# FOTA_MicroController.net
KiCad netlist of a schematic drawn in Altium Designer
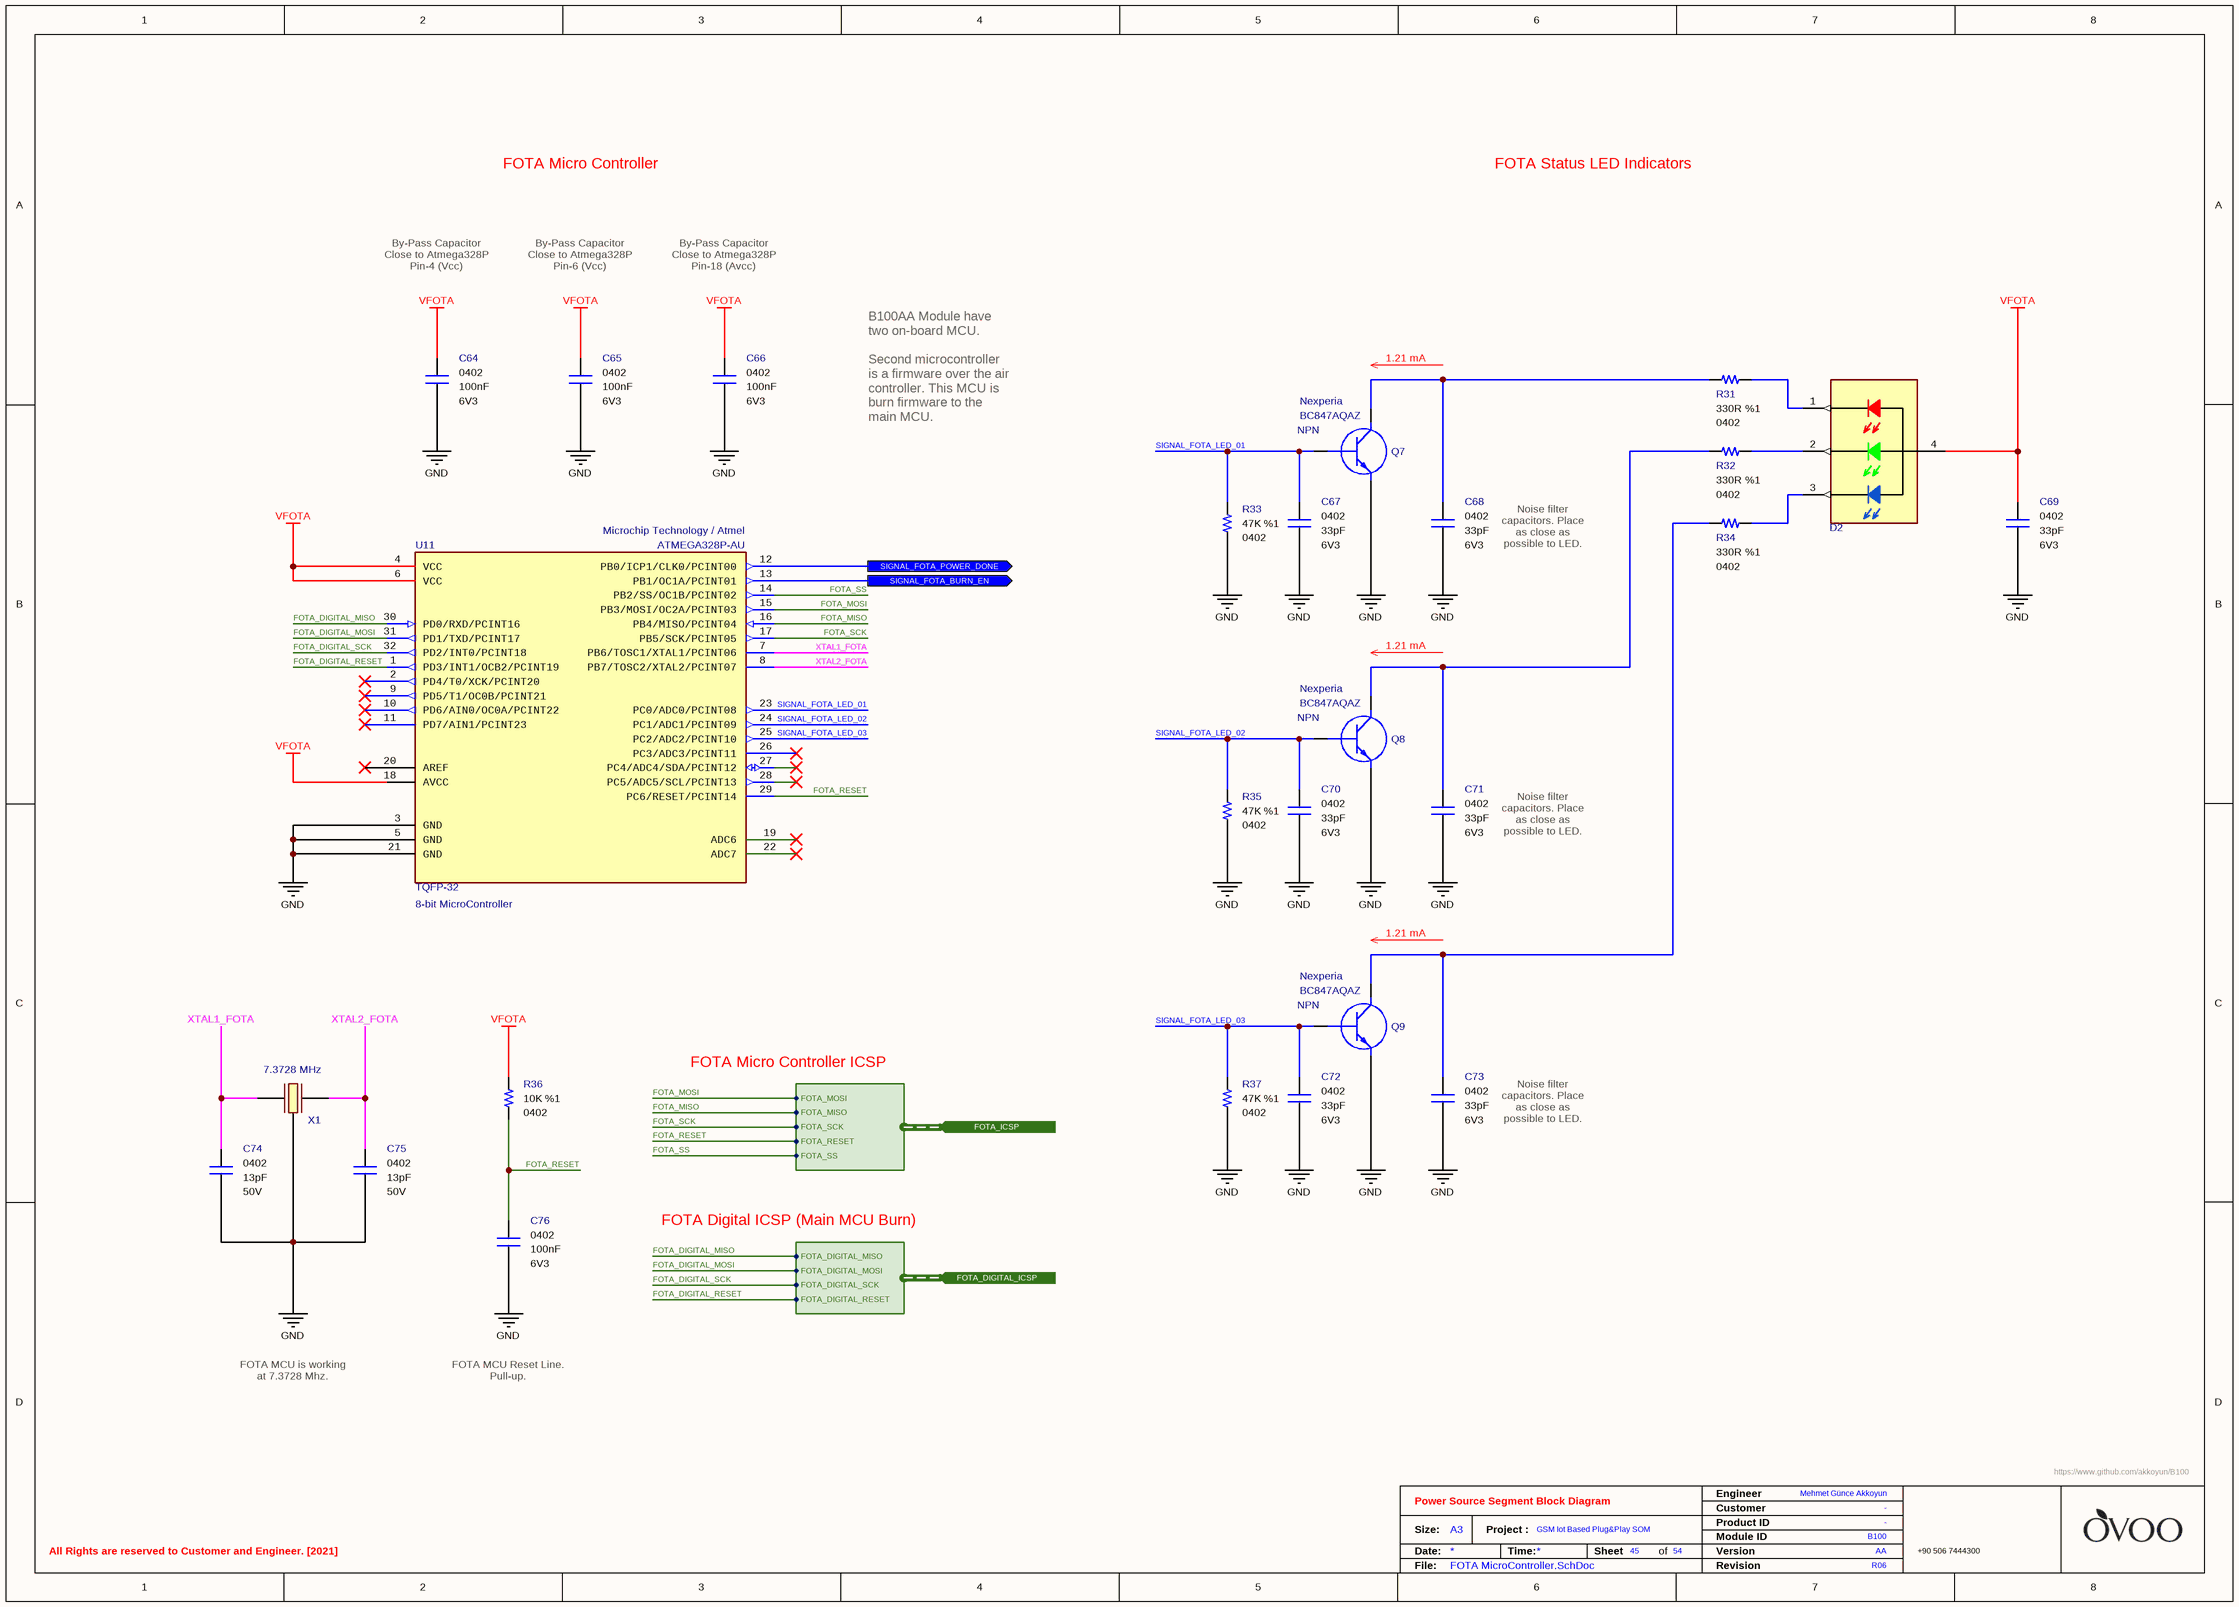
[diagram p0: FOTA MicroController.SchDoc]

(export (version "E")
  (design (tool "Eeschema 10.0.6"))
  (components
    (comp (ref "C64")
      (value "100nF")
      (footprint "CAPACITOR_0402")
      (description "Capacitor - 100nF [0402-6V3] (Ceramic)")
      (fields
        (field (name "TOLERANCE") "%10")
        (field (name "CASE") "0402")
        (field (name "VOLTAGE") "6V3")
        (field (name "MANUFACTURER PART NUMBER") "04026D104KAT4A")
      )
      (libsource (lib "Ovoo_Library") (part "Capacitor - 100nF [0402-6V3]"))
    )
    (comp (ref "C65")
      (value "100nF")
      (footprint "CAPACITOR_0402")
      (description "Capacitor - 100nF [0402-6V3] (Ceramic)")
      (fields
        (field (name "TOLERANCE") "%10")
        (field (name "CASE") "0402")
        (field (name "VOLTAGE") "6V3")
        (field (name "MANUFACTURER PART NUMBER") "04026D104KAT4A")
      )
      (libsource (lib "Ovoo_Library") (part "Capacitor - 100nF [0402-6V3]"))
    )
    (comp (ref "C66")
      (value "100nF")
      (footprint "CAPACITOR_0402")
      (description "Capacitor - 100nF [0402-6V3] (Ceramic)")
      (fields
        (field (name "TOLERANCE") "%10")
        (field (name "CASE") "0402")
        (field (name "VOLTAGE") "6V3")
        (field (name "MANUFACTURER PART NUMBER") "04026D104KAT4A")
      )
      (libsource (lib "Ovoo_Library") (part "Capacitor - 100nF [0402-6V3]"))
    )
    (comp (ref "C67")
      (value "33pF")
      (footprint "CAPACITOR_0402")
      (description "Capacitor - 33pF [0402] (Ceramic)")
      (fields
        (field (name "CASE") "0402")
        (field (name "TOLERANCE") "10%")
        (field (name "VOLTAGE") "6V3")
        (field (name "MANUFACTURER PART NUMBER") "C0402C330J9RACAUTO")
      )
      (libsource (lib "Ovoo_Library") (part "Capacitor - 33pF [0402-6V3]"))
    )
    (comp (ref "C68")
      (value "33pF")
      (footprint "CAPACITOR_0402")
      (description "Capacitor - 33pF [0402] (Ceramic)")
      (fields
        (field (name "CASE") "0402")
        (field (name "TOLERANCE") "10%")
        (field (name "VOLTAGE") "6V3")
        (field (name "MANUFACTURER PART NUMBER") "C0402C330J9RACAUTO")
      )
      (libsource (lib "Ovoo_Library") (part "Capacitor - 33pF [0402-6V3]"))
    )
    (comp (ref "C69")
      (value "33pF")
      (footprint "CAPACITOR_0402")
      (description "Capacitor - 33pF [0402] (Ceramic)")
      (fields
        (field (name "CASE") "0402")
        (field (name "TOLERANCE") "10%")
        (field (name "VOLTAGE") "6V3")
        (field (name "MANUFACTURER PART NUMBER") "C0402C330J9RACAUTO")
      )
      (libsource (lib "Ovoo_Library") (part "Capacitor - 33pF [0402-6V3]"))
    )
    (comp (ref "C70")
      (value "33pF")
      (footprint "CAPACITOR_0402")
      (description "Capacitor - 33pF [0402] (Ceramic)")
      (fields
        (field (name "CASE") "0402")
        (field (name "TOLERANCE") "10%")
        (field (name "VOLTAGE") "6V3")
        (field (name "MANUFACTURER PART NUMBER") "C0402C330J9RACAUTO")
      )
      (libsource (lib "Ovoo_Library") (part "Capacitor - 33pF [0402-6V3]"))
    )
    (comp (ref "C71")
      (value "33pF")
      (footprint "CAPACITOR_0402")
      (description "Capacitor - 33pF [0402] (Ceramic)")
      (fields
        (field (name "CASE") "0402")
        (field (name "TOLERANCE") "10%")
        (field (name "VOLTAGE") "6V3")
        (field (name "MANUFACTURER PART NUMBER") "C0402C330J9RACAUTO")
      )
      (libsource (lib "Ovoo_Library") (part "Capacitor - 33pF [0402-6V3]"))
    )
    (comp (ref "C72")
      (value "33pF")
      (footprint "CAPACITOR_0402")
      (description "Capacitor - 33pF [0402] (Ceramic)")
      (fields
        (field (name "CASE") "0402")
        (field (name "TOLERANCE") "10%")
        (field (name "VOLTAGE") "6V3")
        (field (name "MANUFACTURER PART NUMBER") "C0402C330J9RACAUTO")
      )
      (libsource (lib "Ovoo_Library") (part "Capacitor - 33pF [0402-6V3]"))
    )
    (comp (ref "C73")
      (value "33pF")
      (footprint "CAPACITOR_0402")
      (description "Capacitor - 33pF [0402] (Ceramic)")
      (fields
        (field (name "CASE") "0402")
        (field (name "TOLERANCE") "10%")
        (field (name "VOLTAGE") "6V3")
        (field (name "MANUFACTURER PART NUMBER") "C0402C330J9RACAUTO")
      )
      (libsource (lib "Ovoo_Library") (part "Capacitor - 33pF [0402-6V3]"))
    )
    (comp (ref "C74")
      (value "13pF")
      (footprint "CAPACITOR_0402")
      (description "Capacitor - 13pF [0402] (Ceramic)")
      (fields
        (field (name "TOLERANCE") "1%")
        (field (name "VOLTAGE") "50V")
        (field (name "CASE") "0402")
        (field (name "MANUFACTURER PART NUMBER") "CBR04C130F5GAC")
      )
      (libsource (lib "Ovoo_Library") (part "Capacitor - 13pF [0402-50V]"))
    )
    (comp (ref "C75")
      (value "13pF")
      (footprint "CAPACITOR_0402")
      (description "Capacitor - 13pF [0402] (Ceramic)")
      (fields
        (field (name "TOLERANCE") "1%")
        (field (name "VOLTAGE") "50V")
        (field (name "CASE") "0402")
        (field (name "MANUFACTURER PART NUMBER") "CBR04C130F5GAC")
      )
      (libsource (lib "Ovoo_Library") (part "Capacitor - 13pF [0402-50V]"))
    )
    (comp (ref "C76")
      (value "100nF")
      (footprint "CAPACITOR_0402")
      (description "Capacitor - 100nF [0402-6V3] (Ceramic)")
      (fields
        (field (name "TOLERANCE") "%10")
        (field (name "CASE") "0402")
        (field (name "VOLTAGE") "6V3")
        (field (name "MANUFACTURER PART NUMBER") "04026D104KAT4A")
      )
      (libsource (lib "Ovoo_Library") (part "Capacitor - 100nF [0402-6V3]"))
    )
    (comp (ref "D2")
      (value "150066M153000")
      (footprint "Wurth_0606")
      (description "Standard LEDs - SMD PICOLED series Red LED")
      (fields (field (name "MOUSER PART NUMBER") "710-150066M153000"))
      (libsource (lib "Ovoo_Library") (part "Diode - RGB LED (150066M153000)"))
    )
    (comp (ref "Q7")
      (value "BC847AQAZ")
      (footprint "SOT1215")
      (description "Bipolar NPN Transistors")
      (fields
        (field (name "POLARITY") "NPN")
        (field (name "MANUFACTURER NAME") "Nexperia")
        (field (name "MANUFACTURER PART NUMBER") "BC847AQAZ")
      )
      (libsource (lib "Ovoo_Library") (part "Transistor - BC847"))
    )
    (comp (ref "Q8")
      (value "BC847AQAZ")
      (footprint "SOT1215")
      (description "Bipolar NPN Transistors")
      (fields
        (field (name "POLARITY") "NPN")
        (field (name "MANUFACTURER NAME") "Nexperia")
        (field (name "MANUFACTURER PART NUMBER") "BC847AQAZ")
      )
      (libsource (lib "Ovoo_Library") (part "Transistor - BC847"))
    )
    (comp (ref "Q9")
      (value "BC847AQAZ")
      (footprint "SOT1215")
      (description "Bipolar NPN Transistors")
      (fields
        (field (name "POLARITY") "NPN")
        (field (name "MANUFACTURER NAME") "Nexperia")
        (field (name "MANUFACTURER PART NUMBER") "BC847AQAZ")
      )
      (libsource (lib "Ovoo_Library") (part "Transistor - BC847"))
    )
    (comp (ref "R31")
      (value "330R")
      (footprint "RESISTOR_0402")
      (description "Thick Film Resistors - SMD 1/16 W 330 Ohm 1%")
      (fields
        (field (name "TOLERANCE") "%1")
        (field (name "CASE") "0402")
        (field (name "MANUFACTURER PART NUMBER") "CRCW0402330RFKED")
        (field (name "MOUSER PART NUMBER") "71-CRCW0402-330-E3")
      )
      (libsource (lib "Ovoo_Library") (part "Resistor - 330R"))
    )
    (comp (ref "R32")
      (value "330R")
      (footprint "RESISTOR_0402")
      (description "Thick Film Resistors - SMD 1/16 W 330 Ohm 1%")
      (fields
        (field (name "TOLERANCE") "%1")
        (field (name "CASE") "0402")
        (field (name "MANUFACTURER PART NUMBER") "CRCW0402330RFKED")
        (field (name "MOUSER PART NUMBER") "71-CRCW0402-330-E3")
      )
      (libsource (lib "Ovoo_Library") (part "Resistor - 330R"))
    )
    (comp (ref "R33")
      (value "47K")
      (footprint "RESISTOR_0402")
      (description "Thick Film Resistors - SMD 1/16 W 47 Kohms 1%")
      (fields
        (field (name "TOLERANCE") "%1")
        (field (name "CASE") "0402")
        (field (name "MANUFACTURER PART NUMBER") "CRCW040247K0FKED")
        (field (name "Comment") "47K - 0402 - %1 - 1/16W")
      )
      (libsource (lib "Ovoo_Library") (part "Resistor - 47K"))
    )
    (comp (ref "R34")
      (value "330R")
      (footprint "RESISTOR_0402")
      (description "Thick Film Resistors - SMD 1/16 W 330 Ohm 1%")
      (fields
        (field (name "TOLERANCE") "%1")
        (field (name "CASE") "0402")
        (field (name "MANUFACTURER PART NUMBER") "CRCW0402330RFKED")
        (field (name "MOUSER PART NUMBER") "71-CRCW0402-330-E3")
      )
      (libsource (lib "Ovoo_Library") (part "Resistor - 330R"))
    )
    (comp (ref "R35")
      (value "47K")
      (footprint "RESISTOR_0402")
      (description "Thick Film Resistors - SMD 1/16 W 47 Kohms 1%")
      (fields
        (field (name "TOLERANCE") "%1")
        (field (name "CASE") "0402")
        (field (name "MANUFACTURER PART NUMBER") "CRCW040247K0FKED")
        (field (name "Comment") "47K - 0402 - %1 - 1/16W")
      )
      (libsource (lib "Ovoo_Library") (part "Resistor - 47K"))
    )
    (comp (ref "R36")
      (value "10K")
      (footprint "RESISTOR_0402")
      (description "Thick Film Resistors - SMD 1/16 W 10 Kohms 1%")
      (fields
        (field (name "TOLERANCE") "%1")
        (field (name "CASE") "0402")
        (field (name "MANUFACTURER PART NUMBER") "CRCW040210K0FKED")
        (field (name "MOUSER PART NUMBER") "71-CRCW0402-10K-E3")
      )
      (libsource (lib "Ovoo_Library") (part "Resistor - 10K"))
    )
    (comp (ref "R37")
      (value "47K")
      (footprint "RESISTOR_0402")
      (description "Thick Film Resistors - SMD 1/16 W 47 Kohms 1%")
      (fields
        (field (name "TOLERANCE") "%1")
        (field (name "CASE") "0402")
        (field (name "MANUFACTURER PART NUMBER") "CRCW040247K0FKED")
        (field (name "Comment") "47K - 0402 - %1 - 1/16W")
      )
      (libsource (lib "Ovoo_Library") (part "Resistor - 47K"))
    )
    (comp (ref "U11")
      (value "8-bit MicroController")
      (footprint "TQFP32")
      (description "8-bit Microcontrollers - MCU 32KB In-system Flash 20MHz 1.8V-5.5V")
      (fields
        (field (name "CASE") "TQFP-32")
        (field (name "MOUSER PART NUMBER") "556-ATMEGA328P-AU")
        (field (name "MANUFACTURER PART NUMBER") "ATMEGA328P-AU")
        (field (name "MANUFACTURER NAME") "Microchip Technology / Atmel")
      )
      (libsource (lib "Ovoo_Library") (part "IC - ATMEGA328P"))
    )
    (comp (ref "X1")
      (value "7.3728 MHz")
      (footprint "ABRACON_CRYSTAL")
      (description "Crystals 7.3728MHz 18pF -40C +85C")
      (fields
        (field (name "TOLERANCE") "20 ppm")
        (field (name "MANUFACTURER PART NUMBER") "ABMM2-7.3728MHZ-E2-T")
      )
      (libsource (lib "Ovoo_Library") (part "Crystal - 7.3728 MHz (Abracon)"))
    )
  )
  (nets
    (net (code "3") (name "/FOTA_DIGITAL_MISO") (class "Default")
      (node (ref "U11") (pin "30") (pinfunction "PD0/RXD/PCINT16_30") (pintype "input"))
    )
    (net (code "4") (name "/FOTA_DIGITAL_MOSI") (class "Default")
      (node (ref "U11") (pin "31") (pinfunction "PD1/TXD/PCINT17_31") (pintype "output"))
    )
    (net (code "5") (name "/FOTA_DIGITAL_RESET") (class "Default")
      (node (ref "U11") (pin "1") (pinfunction "PD3/INT1/OCB2/PCINT19_1") (pintype "output"))
    )
    (net (code "6") (name "/FOTA_DIGITAL_SCK") (class "Default")
      (node (ref "U11") (pin "32") (pinfunction "PD2/INT0/PCINT18_32") (pintype "output"))
    )
    (net (code "7") (name "/FOTA_MISO") (class "Default")
      (node (ref "U11") (pin "16") (pinfunction "PB4/MISO/PCINT04_16") (pintype "input"))
    )
    (net (code "8") (name "/FOTA_MOSI") (class "Default")
      (node (ref "U11") (pin "15") (pinfunction "PB3/MOSI/OC2A/PCINT03_15") (pintype "output"))
    )
    (net (code "9") (name "/FOTA_RESET") (class "Default")
      (node (ref "C76") (pin "2") (pinfunction "2_2") (pintype "passive"))
      (node (ref "R36") (pin "1") (pinfunction "1_1") (pintype "passive"))
      (node (ref "U11") (pin "29") (pinfunction "PC6/RESET/PCINT14_29") (pintype "passive"))
    )
    (net (code "10") (name "/FOTA_SCK") (class "Default")
      (node (ref "U11") (pin "17") (pinfunction "PB5/SCK/PCINT05_17") (pintype "output"))
    )
    (net (code "11") (name "/FOTA_SS") (class "Default")
      (node (ref "U11") (pin "14") (pinfunction "PB2/SS/OC1B/PCINT02_14") (pintype "output"))
    )
    (net (code "12") (name "/SIGNAL_FOTA_BURN_EN") (class "Default")
      (node (ref "U11") (pin "13") (pinfunction "PB1/OC1A/PCINT01_13") (pintype "output"))
    )
    (net (code "13") (name "/SIGNAL_FOTA_LED_01") (class "Default")
      (node (ref "C67") (pin "1") (pinfunction "1_1") (pintype "passive"))
      (node (ref "Q7") (pin "1") (pinfunction "B_1") (pintype "passive"))
      (node (ref "R33") (pin "2") (pinfunction "2_2") (pintype "passive"))
      (node (ref "U11") (pin "23") (pinfunction "PC0/ADC0/PCINT08_23") (pintype "output"))
    )
    (net (code "14") (name "/SIGNAL_FOTA_LED_02") (class "Default")
      (node (ref "C70") (pin "1") (pinfunction "1_1") (pintype "passive"))
      (node (ref "Q8") (pin "1") (pinfunction "B_1") (pintype "passive"))
      (node (ref "R35") (pin "2") (pinfunction "2_2") (pintype "passive"))
      (node (ref "U11") (pin "24") (pinfunction "PC1/ADC1/PCINT09_24") (pintype "output"))
    )
    (net (code "15") (name "/SIGNAL_FOTA_LED_03") (class "Default")
      (node (ref "C72") (pin "1") (pinfunction "1_1") (pintype "passive"))
      (node (ref "Q9") (pin "1") (pinfunction "B_1") (pintype "passive"))
      (node (ref "R37") (pin "2") (pinfunction "2_2") (pintype "passive"))
      (node (ref "U11") (pin "25") (pinfunction "PC2/ADC2/PCINT10_25") (pintype "output"))
    )
    (net (code "16") (name "/SIGNAL_FOTA_POWER_DONE") (class "Default")
      (node (ref "U11") (pin "12") (pinfunction "PB0/ICP1/CLK0/PCINT00_12") (pintype "output"))
    )
    (net (code "17") (name "/XTAL1_FOTA") (class "Default")
      (node (ref "C74") (pin "2") (pinfunction "2_2") (pintype "passive"))
      (node (ref "U11") (pin "7") (pinfunction "PB6/TOSC1/XTAL1/PCINT06_7") (pintype "passive"))
      (node (ref "X1") (pin "3") (pinfunction "OUT/IN_3") (pintype "passive"))
    )
    (net (code "18") (name "/XTAL2_FOTA") (class "Default")
      (node (ref "C75") (pin "2") (pinfunction "2_2") (pintype "passive"))
      (node (ref "U11") (pin "8") (pinfunction "PB7/TOSC2/XTAL2/PCINT07_8") (pintype "passive"))
      (node (ref "X1") (pin "1") (pinfunction "IN/OUT_1") (pintype "passive"))
    )
    (net (code "21") (name "GND") (class "Default")
      (node (ref "C64") (pin "1") (pinfunction "1_1") (pintype "passive"))
      (node (ref "C65") (pin "1") (pinfunction "1_1") (pintype "passive"))
      (node (ref "C66") (pin "1") (pinfunction "1_1") (pintype "passive"))
      (node (ref "C67") (pin "2") (pinfunction "2_2") (pintype "passive"))
      (node (ref "C68") (pin "2") (pinfunction "2_2") (pintype "passive"))
      (node (ref "C69") (pin "2") (pinfunction "2_2") (pintype "passive"))
      (node (ref "C70") (pin "2") (pinfunction "2_2") (pintype "passive"))
      (node (ref "C71") (pin "2") (pinfunction "2_2") (pintype "passive"))
      (node (ref "C72") (pin "2") (pinfunction "2_2") (pintype "passive"))
      (node (ref "C73") (pin "2") (pinfunction "2_2") (pintype "passive"))
      (node (ref "C74") (pin "1") (pinfunction "1_1") (pintype "passive"))
      (node (ref "C75") (pin "1") (pinfunction "1_1") (pintype "passive"))
      (node (ref "C76") (pin "1") (pinfunction "1_1") (pintype "passive"))
      (node (ref "Q7") (pin "2") (pinfunction "E_2") (pintype "passive"))
      (node (ref "Q8") (pin "2") (pinfunction "E_2") (pintype "passive"))
      (node (ref "Q9") (pin "2") (pinfunction "E_2") (pintype "passive"))
      (node (ref "R33") (pin "1") (pinfunction "1_1") (pintype "passive"))
      (node (ref "R35") (pin "1") (pinfunction "1_1") (pintype "passive"))
      (node (ref "R37") (pin "1") (pinfunction "1_1") (pintype "passive"))
      (node (ref "U11") (pin "21") (pinfunction "GND_21") (pintype "power_in"))
      (node (ref "U11") (pin "3") (pinfunction "GND_3") (pintype "power_in"))
      (node (ref "U11") (pin "5") (pinfunction "GND_5") (pintype "power_in"))
      (node (ref "X1") (pin "2") (pinfunction "GND_2") (pintype "passive"))
    )
    (net (code "22") (name "Net-(D2-Pad1)") (class "Default")
      (node (ref "D2") (pin "1") (pinfunction "1_1") (pintype "output"))
      (node (ref "R31") (pin "2") (pinfunction "2_2") (pintype "passive"))
    )
    (net (code "23") (name "Net-(D2-Pad2)") (class "Default")
      (node (ref "D2") (pin "2") (pinfunction "2_2") (pintype "output"))
      (node (ref "R32") (pin "2") (pinfunction "2_2") (pintype "passive"))
    )
    (net (code "24") (name "Net-(D2-Pad3)") (class "Default")
      (node (ref "D2") (pin "3") (pinfunction "3_3") (pintype "output"))
      (node (ref "R34") (pin "2") (pinfunction "2_2") (pintype "passive"))
    )
    (net (code "25") (name "Net-(Q7-C)") (class "Default")
      (node (ref "C68") (pin "1") (pinfunction "1_1") (pintype "passive"))
      (node (ref "Q7") (pin "3") (pinfunction "C_3") (pintype "passive"))
      (node (ref "R31") (pin "1") (pinfunction "1_1") (pintype "passive"))
    )
    (net (code "26") (name "Net-(Q8-C)") (class "Default")
      (node (ref "C71") (pin "1") (pinfunction "1_1") (pintype "passive"))
      (node (ref "Q8") (pin "3") (pinfunction "C_3") (pintype "passive"))
      (node (ref "R32") (pin "1") (pinfunction "1_1") (pintype "passive"))
    )
    (net (code "27") (name "Net-(Q9-C)") (class "Default")
      (node (ref "C73") (pin "1") (pinfunction "1_1") (pintype "passive"))
      (node (ref "Q9") (pin "3") (pinfunction "C_3") (pintype "passive"))
      (node (ref "R34") (pin "1") (pinfunction "1_1") (pintype "passive"))
    )
    (net (code "28") (name "VFOTA") (class "Default")
      (node (ref "C64") (pin "2") (pinfunction "2_2") (pintype "passive"))
      (node (ref "C65") (pin "2") (pinfunction "2_2") (pintype "passive"))
      (node (ref "C66") (pin "2") (pinfunction "2_2") (pintype "passive"))
      (node (ref "C69") (pin "1") (pinfunction "1_1") (pintype "passive"))
      (node (ref "D2") (pin "4") (pinfunction "4_4") (pintype "power_in"))
      (node (ref "R36") (pin "2") (pinfunction "2_2") (pintype "passive"))
      (node (ref "U11") (pin "18") (pinfunction "AVCC_18") (pintype "passive"))
      (node (ref "U11") (pin "4") (pinfunction "VCC_4") (pintype "power_in"))
      (node (ref "U11") (pin "6") (pinfunction "VCC_6") (pintype "power_in"))
    )
    (net (code "29") (name "unconnected-(U11-ADC6-Pad19)") (class "Default")
      (node (ref "U11") (pin "19") (pinfunction "ADC6_19") (pintype "passive+no_connect"))
    )
    (net (code "30") (name "unconnected-(U11-ADC7-Pad22)") (class "Default")
      (node (ref "U11") (pin "22") (pinfunction "ADC7_22") (pintype "passive+no_connect"))
    )
    (net (code "31") (name "unconnected-(U11-AREF-Pad20)") (class "Default")
      (node (ref "U11") (pin "20") (pinfunction "AREF_20") (pintype "passive+no_connect"))
    )
    (net (code "32") (name "unconnected-(U11-PC3{slash}ADC3{slash}PCINT11-Pad26)") (class "Default")
      (node (ref "U11") (pin "26") (pinfunction "PC3/ADC3/PCINT11_26") (pintype "passive+no_connect"))
    )
    (net (code "33") (name "unconnected-(U11-PC4{slash}ADC4{slash}SDA{slash}PCINT12-Pad27)") (class "Default")
      (node (ref "U11") (pin "27") (pinfunction "PC4/ADC4/SDA/PCINT12_27") (pintype "bidirectional+no_connect"))
    )
    (net (code "34") (name "unconnected-(U11-PC5{slash}ADC5{slash}SCL{slash}PCINT13-Pad28)") (class "Default")
      (node (ref "U11") (pin "28") (pinfunction "PC5/ADC5/SCL/PCINT13_28") (pintype "output+no_connect"))
    )
    (net (code "35") (name "unconnected-(U11-PD4{slash}T0{slash}XCK{slash}PCINT20-Pad2)") (class "Default")
      (node (ref "U11") (pin "2") (pinfunction "PD4/T0/XCK/PCINT20_2") (pintype "output+no_connect"))
    )
    (net (code "36") (name "unconnected-(U11-PD5{slash}T1{slash}OC0B{slash}PCINT21-Pad9)") (class "Default")
      (node (ref "U11") (pin "9") (pinfunction "PD5/T1/OC0B/PCINT21_9") (pintype "output+no_connect"))
    )
    (net (code "37") (name "unconnected-(U11-PD6{slash}AIN0{slash}OC0A{slash}PCINT22-Pad10)") (class "Default")
      (node (ref "U11") (pin "10") (pinfunction "PD6/AIN0/OC0A/PCINT22_10") (pintype "output+no_connect"))
    )
    (net (code "38") (name "unconnected-(U11-PD7{slash}AIN1{slash}PCINT23-Pad11)") (class "Default")
      (node (ref "U11") (pin "11") (pinfunction "PD7/AIN1/PCINT23_11") (pintype "passive+no_connect"))
    )
    (net (code "39") (name "unconnected-(X1-GND-Pad4)") (class "Default")
      (node (ref "X1") (pin "4") (pinfunction "GND_4") (pintype "passive"))
    )
  )
)
